# untitled.net
KiCad netlist of a schematic drawn in EAGLE
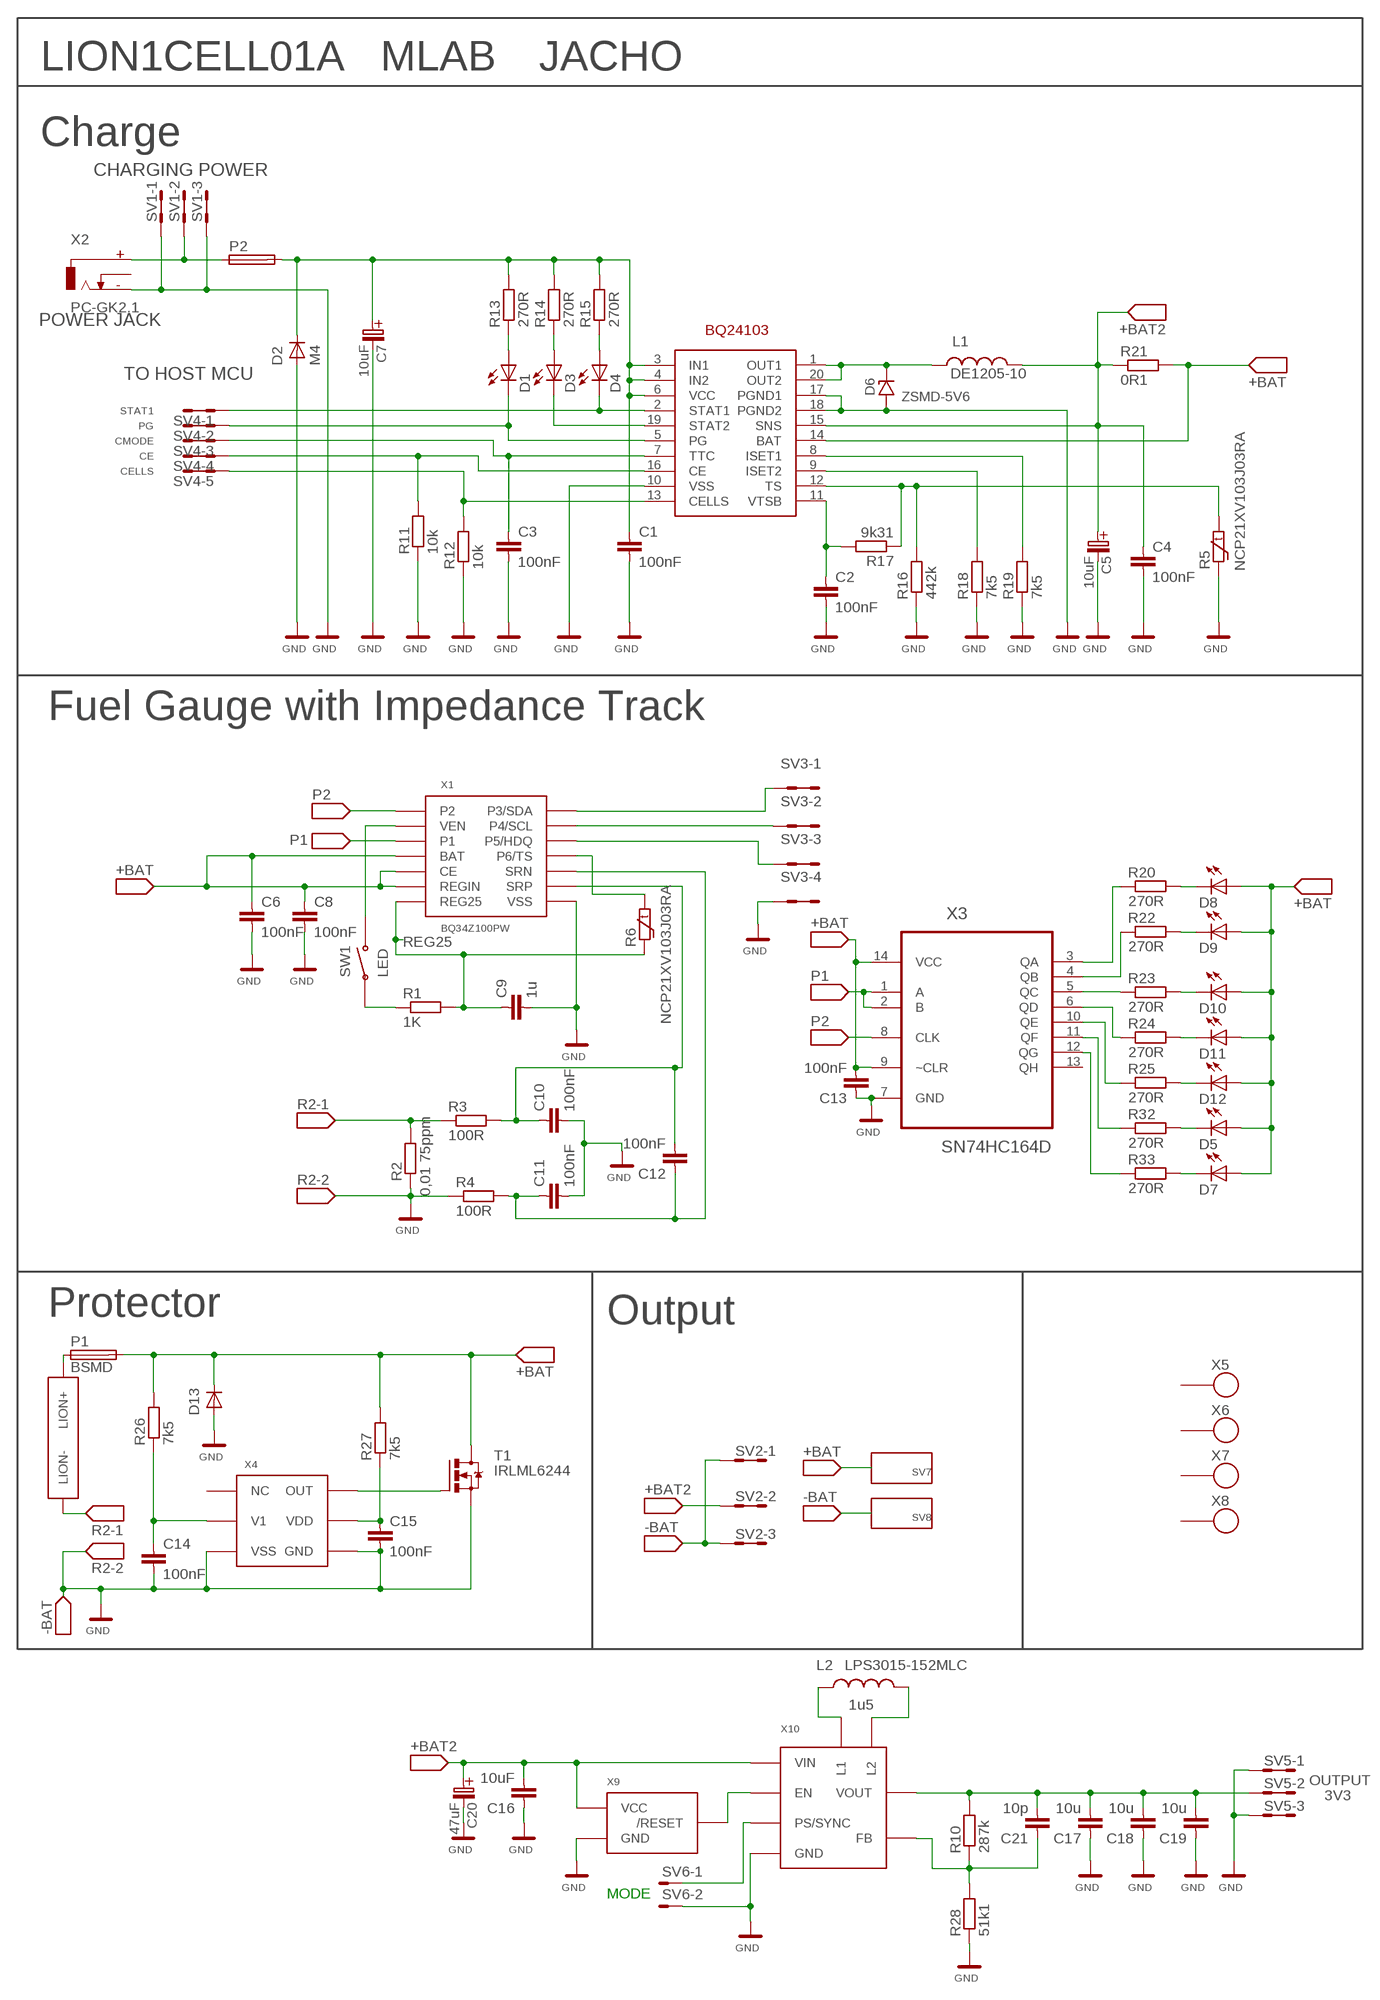
[diagram p0: schematic, sheet 1]

(export (version "E")
  (design (tool "Eeschema 10.0.6"))
  (components
    (comp (ref "C1")
      (value "100nF")
      (footprint "eagle-import:C0805")
      (libsource (lib "eagle-import") (part "C0805"))
    )
    (comp (ref "C2")
      (value "100nF")
      (footprint "eagle-import:C0805")
      (libsource (lib "eagle-import") (part "C0805"))
    )
    (comp (ref "C3")
      (value "100nF")
      (footprint "eagle-import:C0805")
      (libsource (lib "eagle-import") (part "C0805"))
    )
    (comp (ref "C4")
      (value "100nF")
      (footprint "eagle-import:C0805")
      (libsource (lib "eagle-import") (part "C0805"))
    )
    (comp (ref "C5") (value "10uF") (footprint "eagle-import:B") (libsource (lib "eagle-import") (part "B")))
    (comp (ref "C6")
      (value "100nF")
      (footprint "eagle-import:C0805")
      (libsource (lib "eagle-import") (part "C0805"))
    )
    (comp (ref "C7") (value "10uF") (footprint "eagle-import:B") (libsource (lib "eagle-import") (part "B")))
    (comp (ref "C8")
      (value "100nF")
      (footprint "eagle-import:C0805")
      (libsource (lib "eagle-import") (part "C0805"))
    )
    (comp (ref "C9")
      (value "1u")
      (footprint "eagle-import:C0805")
      (libsource (lib "eagle-import") (part "C0805"))
    )
    (comp (ref "C10")
      (value "100nF")
      (footprint "eagle-import:C0805")
      (libsource (lib "eagle-import") (part "C0805"))
    )
    (comp (ref "C11")
      (value "100nF")
      (footprint "eagle-import:C0805")
      (libsource (lib "eagle-import") (part "C0805"))
    )
    (comp (ref "C12")
      (value "100nF")
      (footprint "eagle-import:C0805")
      (libsource (lib "eagle-import") (part "C0805"))
    )
    (comp (ref "C13")
      (value "100nF")
      (footprint "eagle-import:C0805")
      (libsource (lib "eagle-import") (part "C0805"))
    )
    (comp (ref "C14")
      (value "100nF")
      (footprint "eagle-import:C0805")
      (libsource (lib "eagle-import") (part "C0805"))
    )
    (comp (ref "C15")
      (value "100nF")
      (footprint "eagle-import:C0805")
      (libsource (lib "eagle-import") (part "C0805"))
    )
    (comp (ref "C16")
      (value "10uF")
      (footprint "eagle-import:C0805")
      (libsource (lib "eagle-import") (part "C0805"))
    )
    (comp (ref "C17")
      (value "10u")
      (footprint "eagle-import:C0805")
      (libsource (lib "eagle-import") (part "C0805"))
    )
    (comp (ref "C18")
      (value "10u")
      (footprint "eagle-import:C0805")
      (libsource (lib "eagle-import") (part "C0805"))
    )
    (comp (ref "C19")
      (value "10u")
      (footprint "eagle-import:C0805")
      (libsource (lib "eagle-import") (part "C0805"))
    )
    (comp (ref "C20") (value "47uF") (footprint "eagle-import:B") (libsource (lib "eagle-import") (part "B")))
    (comp (ref "C21")
      (value "10p")
      (footprint "eagle-import:0603")
      (libsource (lib "eagle-import") (part "C0603"))
    )
    (comp (ref "D1")
      (value "LED1206_2")
      (footprint "eagle-import:1206_2")
      (libsource (lib "eagle-import") (part "LED1206_2"))
    )
    (comp (ref "D2")
      (value "M4")
      (footprint "eagle-import:SMB")
      (libsource (lib "eagle-import") (part "D-OB."))
    )
    (comp (ref "D3")
      (value "LED1206_2")
      (footprint "eagle-import:1206_2")
      (libsource (lib "eagle-import") (part "LED1206_2"))
    )
    (comp (ref "D4")
      (value "LED1206_2")
      (footprint "eagle-import:1206_2")
      (libsource (lib "eagle-import") (part "LED1206_2"))
    )
    (comp (ref "D5")
      (value "LED1206_2")
      (footprint "eagle-import:1206_2")
      (libsource (lib "eagle-import") (part "LED1206_2"))
    )
    (comp (ref "D6")
      (value "ZSMD-5V6")
      (footprint "eagle-import:MINIMELF")
      (libsource (lib "eagle-import") (part "D-ZENEROVA"))
    )
    (comp (ref "D7")
      (value "LED1206_2")
      (footprint "eagle-import:1206_2")
      (libsource (lib "eagle-import") (part "LED1206_2"))
    )
    (comp (ref "D8")
      (value "LED1206_2")
      (footprint "eagle-import:1206_2")
      (libsource (lib "eagle-import") (part "LED1206_2"))
    )
    (comp (ref "D9")
      (value "LED1206_2")
      (footprint "eagle-import:1206_2")
      (libsource (lib "eagle-import") (part "LED1206_2"))
    )
    (comp (ref "D10")
      (value "LED1206_2")
      (footprint "eagle-import:1206_2")
      (libsource (lib "eagle-import") (part "LED1206_2"))
    )
    (comp (ref "D11")
      (value "LED1206_2")
      (footprint "eagle-import:1206_2")
      (libsource (lib "eagle-import") (part "LED1206_2"))
    )
    (comp (ref "D12")
      (value "LED1206_2")
      (footprint "eagle-import:1206_2")
      (libsource (lib "eagle-import") (part "LED1206_2"))
    )
    (comp (ref "D13")
      (value "D-OB.SMA")
      (footprint "eagle-import:SMA")
      (libsource (lib "eagle-import") (part "D-OB.SMA"))
    )
    (comp (ref "L1")
      (value "DE1205-10")
      (footprint "eagle-import:DE1205-10")
      (libsource (lib "eagle-import") (part "DE1205-10"))
    )
    (comp (ref "L2")
      (value "LPS3015-152MLC")
      (footprint "eagle-import:LPS3015")
      (libsource (lib "eagle-import") (part "LPS3015"))
    )
    (comp (ref "P1")
      (value "BSMD")
      (footprint "eagle-import:2410")
      (libsource (lib "eagle-import") (part "POJISTKA2410"))
    )
    (comp (ref "P2")
      (value "POJISTKA_1812")
      (footprint "eagle-import:1812")
      (libsource (lib "eagle-import") (part "POJISTKA_1812"))
    )
    (comp (ref "R1")
      (value "1K")
      (footprint "eagle-import:0805")
      (libsource (lib "eagle-import") (part "R0805"))
    )
    (comp (ref "R2")
      (value "0,01 75ppm")
      (footprint "eagle-import:0805")
      (libsource (lib "eagle-import") (part "R0805"))
    )
    (comp (ref "R3")
      (value "100R")
      (footprint "eagle-import:0805")
      (libsource (lib "eagle-import") (part "R0805"))
    )
    (comp (ref "R4")
      (value "100R")
      (footprint "eagle-import:0805")
      (libsource (lib "eagle-import") (part "R0805"))
    )
    (comp (ref "R5")
      (value "NCP21XV103J03RA")
      (footprint "eagle-import:0805")
      (libsource (lib "eagle-import") (part "TERMISTOR0805"))
    )
    (comp (ref "R6")
      (value "NCP21XV103J03RA")
      (footprint "eagle-import:0805")
      (libsource (lib "eagle-import") (part "TERMISTOR0805"))
    )
    (comp (ref "R10")
      (value "287k")
      (footprint "eagle-import:0603")
      (libsource (lib "eagle-import") (part "R0603"))
    )
    (comp (ref "R11")
      (value "10k")
      (footprint "eagle-import:0805")
      (libsource (lib "eagle-import") (part "R0805"))
    )
    (comp (ref "R12")
      (value "10k")
      (footprint "eagle-import:0805")
      (libsource (lib "eagle-import") (part "R0805"))
    )
    (comp (ref "R13")
      (value "270R")
      (footprint "eagle-import:0805")
      (libsource (lib "eagle-import") (part "R0805"))
    )
    (comp (ref "R14")
      (value "270R")
      (footprint "eagle-import:0805")
      (libsource (lib "eagle-import") (part "R0805"))
    )
    (comp (ref "R15")
      (value "270R")
      (footprint "eagle-import:0805")
      (libsource (lib "eagle-import") (part "R0805"))
    )
    (comp (ref "R16")
      (value "442k")
      (footprint "eagle-import:0805")
      (libsource (lib "eagle-import") (part "R0805"))
    )
    (comp (ref "R17")
      (value "9k31")
      (footprint "eagle-import:0805")
      (libsource (lib "eagle-import") (part "R0805"))
    )
    (comp (ref "R18")
      (value "7k5")
      (footprint "eagle-import:0805")
      (libsource (lib "eagle-import") (part "R0805"))
    )
    (comp (ref "R19")
      (value "7k5")
      (footprint "eagle-import:0805")
      (libsource (lib "eagle-import") (part "R0805"))
    )
    (comp (ref "R20")
      (value "270R")
      (footprint "eagle-import:0805")
      (libsource (lib "eagle-import") (part "R0805"))
    )
    (comp (ref "R21")
      (value "0R1")
      (footprint "eagle-import:R2512")
      (libsource (lib "eagle-import") (part "R-EU_R2512"))
    )
    (comp (ref "R22")
      (value "270R")
      (footprint "eagle-import:0805")
      (libsource (lib "eagle-import") (part "R0805"))
    )
    (comp (ref "R23")
      (value "270R")
      (footprint "eagle-import:0805")
      (libsource (lib "eagle-import") (part "R0805"))
    )
    (comp (ref "R24")
      (value "270R")
      (footprint "eagle-import:0805")
      (libsource (lib "eagle-import") (part "R0805"))
    )
    (comp (ref "R25")
      (value "270R")
      (footprint "eagle-import:0805")
      (libsource (lib "eagle-import") (part "R0805"))
    )
    (comp (ref "R26")
      (value "7k5")
      (footprint "eagle-import:0805")
      (libsource (lib "eagle-import") (part "R0805"))
    )
    (comp (ref "R27")
      (value "7k5")
      (footprint "eagle-import:0805")
      (libsource (lib "eagle-import") (part "R0805"))
    )
    (comp (ref "R28")
      (value "51k1")
      (footprint "eagle-import:0603")
      (libsource (lib "eagle-import") (part "R0603"))
    )
    (comp (ref "R32")
      (value "270R")
      (footprint "eagle-import:0805")
      (libsource (lib "eagle-import") (part "R0805"))
    )
    (comp (ref "R33")
      (value "270R")
      (footprint "eagle-import:0805")
      (libsource (lib "eagle-import") (part "R0805"))
    )
    (comp (ref "SV1")
      (value "MA03-2")
      (footprint "eagle-import:MA03-2")
      (libsource (lib "eagle-import") (part "MA03-2"))
    )
    (comp (ref "SV2")
      (value "MA03-2")
      (footprint "eagle-import:MA03-2")
      (libsource (lib "eagle-import") (part "MA03-2"))
    )
    (comp (ref "SV3")
      (value "MA04-2")
      (footprint "eagle-import:MA04-2")
      (libsource (lib "eagle-import") (part "MA04-2"))
    )
    (comp (ref "SV4")
      (value "MA05-2")
      (footprint "eagle-import:MA05-2")
      (libsource (lib "eagle-import") (part "MA05-2"))
    )
    (comp (ref "SV5")
      (value "MA03-2")
      (footprint "eagle-import:MA03-2")
      (libsource (lib "eagle-import") (part "MA03-2"))
    )
    (comp (ref "SV6")
      (value "MA02-1")
      (footprint "eagle-import:MA02-1")
      (libsource (lib "eagle-import") (part "MA02-1"))
    )
    (comp (ref "SV7")
      (value "WAGO256")
      (footprint "eagle-import:WAGO256")
      (libsource (lib "eagle-import") (part "WAGO256"))
    )
    (comp (ref "SV8")
      (value "WAGO256")
      (footprint "eagle-import:WAGO256")
      (libsource (lib "eagle-import") (part "WAGO256"))
    )
    (comp (ref "SW1")
      (value "TACT-64K")
      (footprint "eagle-import:TACT-64K")
      (libsource (lib "eagle-import") (part "TACT-64K"))
    )
    (comp (ref "T1")
      (value "IRLML6244")
      (footprint "eagle-import:SOT23")
      (libsource (lib "eagle-import") (part "IRLML6244TRPBF"))
    )
    (comp (ref "U$2")
      (value "LION1")
      (footprint "eagle-import:LION1")
      (libsource (lib "eagle-import") (part "LION1"))
    )
    (comp (ref "U1")
      (value "BQ24103")
      (footprint "eagle-import:RHL_R-VQFN-N20")
      (libsource (lib "eagle-import") (part "BQ24103"))
    )
    (comp (ref "X1")
      (value "BQ34Z100PW")
      (footprint "eagle-import:TSSOP14")
      (libsource (lib "eagle-import") (part "BQ34Z100PW"))
    )
    (comp (ref "X2")
      (value "DC2.1MM")
      (footprint "eagle-import:DC2.1MM")
      (libsource (lib "eagle-import") (part "DC2.1MM"))
    )
    (comp (ref "X3")
      (value "SN74HC164D")
      (footprint "eagle-import:SOIC127P600X175-14N")
      (libsource (lib "eagle-import") (part "SN74HC164D"))
    )
    (comp (ref "X4")
      (value "BQ294602")
      (footprint "eagle-import:SON_N6")
      (libsource (lib "eagle-import") (part "BQ294602"))
    )
    (comp (ref "X5")
      (value "SROUB3M")
      (footprint "eagle-import:SROUB3M")
      (libsource (lib "eagle-import") (part "SROUB3M"))
    )
    (comp (ref "X6")
      (value "SROUB3M")
      (footprint "eagle-import:SROUB3M")
      (libsource (lib "eagle-import") (part "SROUB3M"))
    )
    (comp (ref "X7")
      (value "SROUB3M")
      (footprint "eagle-import:SROUB3M")
      (libsource (lib "eagle-import") (part "SROUB3M"))
    )
    (comp (ref "X8")
      (value "SROUB3M")
      (footprint "eagle-import:SROUB3M")
      (libsource (lib "eagle-import") (part "SROUB3M"))
    )
    (comp (ref "X9")
      (value "APX809-26SA")
      (footprint "eagle-import:SOT23")
      (libsource (lib "eagle-import") (part "APX809-26SA"))
    )
    (comp (ref "X10")
      (value "TPS63036")
      (footprint "eagle-import:DSBGA8")
      (libsource (lib "eagle-import") (part "TPS63036"))
    )
  )
  (nets
    (net (code "1") (name "/+BAT") (class "Default")
      (node (ref "C13") (pin "2") (pinfunction "2_2") (pintype "passive"))
      (node (ref "C6") (pin "1") (pinfunction "1_1") (pintype "passive"))
      (node (ref "C8") (pin "1") (pinfunction "1_1") (pintype "passive"))
      (node (ref "D10") (pin "A") (pinfunction "A_A") (pintype "passive"))
      (node (ref "D11") (pin "A") (pinfunction "A_A") (pintype "passive"))
      (node (ref "D12") (pin "A") (pinfunction "A_A") (pintype "passive"))
      (node (ref "D13") (pin "K") (pinfunction "C_K") (pintype "passive"))
      (node (ref "D5") (pin "A") (pinfunction "A_A") (pintype "passive"))
      (node (ref "D7") (pin "A") (pinfunction "A_A") (pintype "passive"))
      (node (ref "D8") (pin "A") (pinfunction "A_A") (pintype "passive"))
      (node (ref "D9") (pin "A") (pinfunction "A_A") (pintype "passive"))
      (node (ref "P1") (pin "2") (pinfunction "2_2") (pintype "passive"))
      (node (ref "R21") (pin "2") (pinfunction "2_2") (pintype "passive"))
      (node (ref "R26") (pin "2") (pinfunction "2_2") (pintype "passive"))
      (node (ref "R27") (pin "2") (pinfunction "2_2") (pintype "passive"))
      (node (ref "SV7") (pin "1") (pinfunction "P$1_1") (pintype "passive"))
      (node (ref "SV7") (pin "A1") (pinfunction "P$1_A1") (pintype "passive"))
      (node (ref "T1") (pin "3") (pinfunction "D_3") (pintype "passive"))
      (node (ref "U1") (pin "14") (pinfunction "BAT_14") (pintype "bidirectional"))
      (node (ref "X1") (pin "4") (pinfunction "BAT_4") (pintype "bidirectional"))
      (node (ref "X1") (pin "5") (pinfunction "CE_5") (pintype "bidirectional"))
      (node (ref "X1") (pin "6") (pinfunction "REGIN_6") (pintype "bidirectional"))
      (node (ref "X3") (pin "14") (pinfunction "VCC_14") (pintype "power_in"))
      (node (ref "X3") (pin "9") (pinfunction "~{CLR}_9") (pintype "input"))
    )
    (net (code "2") (name "/+BAT2") (class "Default")
      (node (ref "C16") (pin "2") (pinfunction "2_2") (pintype "passive"))
      (node (ref "C20") (pin "+") (pinfunction "C_EL+_+") (pintype "passive"))
      (node (ref "C4") (pin "1") (pinfunction "1_1") (pintype "passive"))
      (node (ref "C5") (pin "+") (pinfunction "C_EL+_+") (pintype "passive"))
      (node (ref "L1") (pin "P$2") (pinfunction "2_P$2") (pintype "passive"))
      (node (ref "R21") (pin "1") (pinfunction "1_1") (pintype "passive"))
      (node (ref "SV2") (pin "3") (pinfunction "K_3") (pintype "passive"))
      (node (ref "SV2") (pin "4") (pinfunction "K_4") (pintype "passive"))
      (node (ref "U1") (pin "15") (pinfunction "SNS_15") (pintype "bidirectional"))
      (node (ref "X10") (pin "A1") (pinfunction "VIN_A1") (pintype "input"))
      (node (ref "X9") (pin "3") (pinfunction "VCC_3") (pintype "input"))
    )
    (net (code "3") (name "/P1") (class "Default")
      (node (ref "X1") (pin "3") (pinfunction "P1_3") (pintype "bidirectional"))
      (node (ref "X3") (pin "1") (pinfunction "A_1") (pintype "input"))
      (node (ref "X3") (pin "2") (pinfunction "B_2") (pintype "input"))
    )
    (net (code "4") (name "/P2") (class "Default")
      (node (ref "X1") (pin "1") (pinfunction "P2_1") (pintype "bidirectional"))
      (node (ref "X3") (pin "8") (pinfunction "CLK_8") (pintype "input"))
    )
    (net (code "5") (name "/R2") (class "Default")
      (node (ref "R2") (pin "2") (pinfunction "2_2") (pintype "passive"))
      (node (ref "R3") (pin "1") (pinfunction "1_1") (pintype "passive"))
      (node (ref "U$2") (pin "-") (pinfunction "LION-_-") (pintype "bidirectional"))
      (node (ref "U$2") (pin "-1") (pinfunction "LION-_-1") (pintype "bidirectional"))
    )
    (net (code "6") (name "GND") (class "Default")
      (node (ref "C1") (pin "2") (pinfunction "2_2") (pintype "passive"))
      (node (ref "C10") (pin "2") (pinfunction "2_2") (pintype "passive"))
      (node (ref "C11") (pin "2") (pinfunction "2_2") (pintype "passive"))
      (node (ref "C13") (pin "1") (pinfunction "1_1") (pintype "passive"))
      (node (ref "C14") (pin "2") (pinfunction "2_2") (pintype "passive"))
      (node (ref "C15") (pin "2") (pinfunction "2_2") (pintype "passive"))
      (node (ref "C16") (pin "1") (pinfunction "1_1") (pintype "passive"))
      (node (ref "C17") (pin "1") (pinfunction "1_1") (pintype "passive"))
      (node (ref "C18") (pin "1") (pinfunction "1_1") (pintype "passive"))
      (node (ref "C19") (pin "1") (pinfunction "1_1") (pintype "passive"))
      (node (ref "C2") (pin "2") (pinfunction "2_2") (pintype "passive"))
      (node (ref "C20") (pin "-") (pinfunction "C_EL-_-") (pintype "passive"))
      (node (ref "C3") (pin "2") (pinfunction "2_2") (pintype "passive"))
      (node (ref "C4") (pin "2") (pinfunction "2_2") (pintype "passive"))
      (node (ref "C5") (pin "-") (pinfunction "C_EL-_-") (pintype "passive"))
      (node (ref "C6") (pin "2") (pinfunction "2_2") (pintype "passive"))
      (node (ref "C7") (pin "-") (pinfunction "C_EL-_-") (pintype "passive"))
      (node (ref "C8") (pin "2") (pinfunction "2_2") (pintype "passive"))
      (node (ref "C9") (pin "2") (pinfunction "2_2") (pintype "passive"))
      (node (ref "D13") (pin "A") (pinfunction "A_A") (pintype "passive"))
      (node (ref "D2") (pin "A") (pinfunction "A_A") (pintype "passive"))
      (node (ref "D6") (pin "A") (pinfunction "A_A") (pintype "passive"))
      (node (ref "R11") (pin "1") (pinfunction "1_1") (pintype "passive"))
      (node (ref "R12") (pin "1") (pinfunction "1_1") (pintype "passive"))
      (node (ref "R16") (pin "1") (pinfunction "1_1") (pintype "passive"))
      (node (ref "R18") (pin "1") (pinfunction "1_1") (pintype "passive"))
      (node (ref "R19") (pin "1") (pinfunction "1_1") (pintype "passive"))
      (node (ref "R2") (pin "1") (pinfunction "1_1") (pintype "passive"))
      (node (ref "R28") (pin "1") (pinfunction "1_1") (pintype "passive"))
      (node (ref "R4") (pin "1") (pinfunction "1_1") (pintype "passive"))
      (node (ref "R5") (pin "1") (pinfunction "1_1") (pintype "passive"))
      (node (ref "SV1") (pin "1") (pinfunction "K_1") (pintype "passive"))
      (node (ref "SV1") (pin "2") (pinfunction "K_2") (pintype "passive"))
      (node (ref "SV1") (pin "5") (pinfunction "K_5") (pintype "passive"))
      (node (ref "SV1") (pin "6") (pinfunction "K_6") (pintype "passive"))
      (node (ref "SV2") (pin "1") (pinfunction "K_1") (pintype "passive"))
      (node (ref "SV2") (pin "2") (pinfunction "K_2") (pintype "passive"))
      (node (ref "SV2") (pin "5") (pinfunction "K_5") (pintype "passive"))
      (node (ref "SV2") (pin "6") (pinfunction "K_6") (pintype "passive"))
      (node (ref "SV3") (pin "7") (pinfunction "K_7") (pintype "passive"))
      (node (ref "SV3") (pin "8") (pinfunction "K_8") (pintype "passive"))
      (node (ref "SV5") (pin "1") (pinfunction "K_1") (pintype "passive"))
      (node (ref "SV5") (pin "2") (pinfunction "K_2") (pintype "passive"))
      (node (ref "SV5") (pin "5") (pinfunction "K_5") (pintype "passive"))
      (node (ref "SV5") (pin "6") (pinfunction "K_6") (pintype "passive"))
      (node (ref "SV6") (pin "2") (pinfunction "P$1_2") (pintype "passive"))
      (node (ref "SV8") (pin "1") (pinfunction "P$1_1") (pintype "passive"))
      (node (ref "SV8") (pin "A1") (pinfunction "P$1_A1") (pintype "passive"))
      (node (ref "T1") (pin "2") (pinfunction "S_2") (pintype "passive"))
      (node (ref "U1") (pin "10") (pinfunction "VSS_10") (pintype "bidirectional"))
      (node (ref "U1") (pin "17") (pinfunction "PGND1_17") (pintype "bidirectional"))
      (node (ref "U1") (pin "18") (pinfunction "PGND2_18") (pintype "bidirectional"))
      (node (ref "X1") (pin "8") (pinfunction "VSS_8") (pintype "bidirectional"))
      (node (ref "X10") (pin "C2") (pinfunction "GND_C2") (pintype "passive"))
      (node (ref "X2") (pin "GND") (pinfunction "-_GND") (pintype "passive"))
      (node (ref "X3") (pin "7") (pinfunction "GND_7") (pintype "passive"))
      (node (ref "X4") (pin "3") (pinfunction "VSS_3") (pintype "bidirectional"))
      (node (ref "X4") (pin "4") (pinfunction "VSS_4") (pintype "bidirectional"))
      (node (ref "X4") (pin "7") (pinfunction "GND_7") (pintype "bidirectional"))
      (node (ref "X9") (pin "1") (pinfunction "GND_1") (pintype "passive"))
    )
    (net (code "7") (name "Net-(C7-C_EL+)") (class "Default")
      (node (ref "C1") (pin "1") (pinfunction "1_1") (pintype "passive"))
      (node (ref "C7") (pin "+") (pinfunction "C_EL+_+") (pintype "passive"))
      (node (ref "D2") (pin "K") (pinfunction "C_K") (pintype "passive"))
      (node (ref "P2") (pin "2") (pinfunction "2_2") (pintype "passive"))
      (node (ref "R13") (pin "2") (pinfunction "2_2") (pintype "passive"))
      (node (ref "R14") (pin "2") (pinfunction "2_2") (pintype "passive"))
      (node (ref "R15") (pin "2") (pinfunction "2_2") (pintype "passive"))
      (node (ref "U1") (pin "3") (pinfunction "IN1_3") (pintype "bidirectional"))
      (node (ref "U1") (pin "4") (pinfunction "IN2_4") (pintype "bidirectional"))
      (node (ref "U1") (pin "6") (pinfunction "VCC_6") (pintype "bidirectional"))
    )
    (net (code "8") (name "Net-(D1-C)") (class "Default")
      (node (ref "D1") (pin "K") (pinfunction "C_K") (pintype "passive"))
      (node (ref "SV4") (pin "3") (pinfunction "K_3") (pintype "passive"))
      (node (ref "SV4") (pin "4") (pinfunction "K_4") (pintype "passive"))
      (node (ref "U1") (pin "5") (pinfunction "PG_5") (pintype "bidirectional"))
    )
    (net (code "9") (name "Net-(D1-PadA)") (class "Default")
      (node (ref "D1") (pin "A") (pinfunction "A_A") (pintype "passive"))
      (node (ref "R13") (pin "1") (pinfunction "1_1") (pintype "passive"))
    )
    (net (code "10") (name "Net-(D3-C)") (class "Default")
      (node (ref "D3") (pin "K") (pinfunction "C_K") (pintype "passive"))
      (node (ref "U1") (pin "19") (pinfunction "STAT2_19") (pintype "bidirectional"))
    )
    (net (code "11") (name "Net-(D3-PadA)") (class "Default")
      (node (ref "D3") (pin "A") (pinfunction "A_A") (pintype "passive"))
      (node (ref "R14") (pin "1") (pinfunction "1_1") (pintype "passive"))
    )
    (net (code "12") (name "Net-(D4-C)") (class "Default")
      (node (ref "D4") (pin "K") (pinfunction "C_K") (pintype "passive"))
      (node (ref "SV4") (pin "1") (pinfunction "K_1") (pintype "passive"))
      (node (ref "SV4") (pin "2") (pinfunction "K_2") (pintype "passive"))
      (node (ref "U1") (pin "2") (pinfunction "STAT1_2") (pintype "bidirectional"))
    )
    (net (code "13") (name "Net-(D4-PadA)") (class "Default")
      (node (ref "D4") (pin "A") (pinfunction "A_A") (pintype "passive"))
      (node (ref "R15") (pin "1") (pinfunction "1_1") (pintype "passive"))
    )
    (net (code "14") (name "Net-(D5-C)") (class "Default")
      (node (ref "D5") (pin "K") (pinfunction "C_K") (pintype "passive"))
      (node (ref "R32") (pin "2") (pinfunction "2_2") (pintype "passive"))
    )
    (net (code "15") (name "Net-(D6-K)") (class "Default")
      (node (ref "D6") (pin "C") (pinfunction "K_C") (pintype "passive"))
      (node (ref "L1") (pin "P$1") (pinfunction "1_P$1") (pintype "passive"))
      (node (ref "U1") (pin "1") (pinfunction "OUT1_1") (pintype "bidirectional"))
      (node (ref "U1") (pin "20") (pinfunction "OUT2_20") (pintype "bidirectional"))
    )
    (net (code "16") (name "Net-(D7-C)") (class "Default")
      (node (ref "D7") (pin "K") (pinfunction "C_K") (pintype "passive"))
      (node (ref "R33") (pin "2") (pinfunction "2_2") (pintype "passive"))
    )
    (net (code "17") (name "Net-(D8-C)") (class "Default")
      (node (ref "D8") (pin "K") (pinfunction "C_K") (pintype "passive"))
      (node (ref "R20") (pin "2") (pinfunction "2_2") (pintype "passive"))
    )
    (net (code "18") (name "Net-(D9-C)") (class "Default")
      (node (ref "D9") (pin "K") (pinfunction "C_K") (pintype "passive"))
      (node (ref "R22") (pin "2") (pinfunction "2_2") (pintype "passive"))
    )
    (net (code "19") (name "Net-(D10-C)") (class "Default")
      (node (ref "D10") (pin "K") (pinfunction "C_K") (pintype "passive"))
      (node (ref "R23") (pin "2") (pinfunction "2_2") (pintype "passive"))
    )
    (net (code "20") (name "Net-(D11-C)") (class "Default")
      (node (ref "D11") (pin "K") (pinfunction "C_K") (pintype "passive"))
      (node (ref "R24") (pin "2") (pinfunction "2_2") (pintype "passive"))
    )
    (net (code "21") (name "Net-(D12-C)") (class "Default")
      (node (ref "D12") (pin "K") (pinfunction "C_K") (pintype "passive"))
      (node (ref "R25") (pin "2") (pinfunction "2_2") (pintype "passive"))
    )
    (net (code "22") (name "Net-(P1-Pad1)") (class "Default")
      (node (ref "P1") (pin "1") (pinfunction "1_1") (pintype "passive"))
      (node (ref "U$2") (pin "+") (pinfunction "LION+_+") (pintype "bidirectional"))
      (node (ref "U$2") (pin "+1") (pinfunction "LION+_+1") (pintype "bidirectional"))
    )
    (net (code "23") (name "Net-(P2-Pad1)") (class "Default")
      (node (ref "P2") (pin "1") (pinfunction "1_1") (pintype "passive"))
      (node (ref "SV1") (pin "3") (pinfunction "K_3") (pintype "passive"))
      (node (ref "SV1") (pin "4") (pinfunction "K_4") (pintype "passive"))
      (node (ref "X2") (pin "+") (pinfunction "+_+") (pintype "passive"))
    )
    (net (code "24") (name "Net-(R1-Pad1)") (class "Default")
      (node (ref "R1") (pin "1") (pinfunction "1_1") (pintype "passive"))
      (node (ref "SW1") (pin "P$1") (pinfunction "P$1_P$1") (pintype "passive"))
      (node (ref "SW1") (pin "P$2") (pinfunction "P$1_P$2") (pintype "passive"))
    )
    (net (code "25") (name "Net-(SV6A-P$1)") (class "Default")
      (node (ref "SV6") (pin "1") (pinfunction "P$1_1") (pintype "passive"))
      (node (ref "X10") (pin "B2") (pinfunction "PS/SYNC_B2") (pintype "input"))
    )
    (net (code "26") (name "Net-(T1-G)") (class "Default")
      (node (ref "T1") (pin "1") (pinfunction "G_1") (pintype "passive"))
      (node (ref "X4") (pin "6") (pinfunction "OUT_6") (pintype "bidirectional"))
    )
    (net (code "27") (name "Net-(U1-CE)") (class "Default")
      (node (ref "R11") (pin "2") (pinfunction "2_2") (pintype "passive"))
      (node (ref "SV4") (pin "7") (pinfunction "K_7") (pintype "passive"))
      (node (ref "SV4") (pin "8") (pinfunction "K_8") (pintype "passive"))
      (node (ref "U1") (pin "16") (pinfunction "CE_16") (pintype "bidirectional"))
    )
    (net (code "28") (name "Net-(U1-CELLS)") (class "Default")
      (node (ref "R12") (pin "2") (pinfunction "2_2") (pintype "passive"))
      (node (ref "SV4") (pin "10") (pinfunction "K_10") (pintype "passive"))
      (node (ref "SV4") (pin "9") (pinfunction "K_9") (pintype "passive"))
      (node (ref "U1") (pin "13") (pinfunction "CELLS_13") (pintype "bidirectional"))
    )
    (net (code "29") (name "Net-(U1-ISET1)") (class "Default")
      (node (ref "R19") (pin "2") (pinfunction "2_2") (pintype "passive"))
      (node (ref "U1") (pin "8") (pinfunction "ISET1_8") (pintype "bidirectional"))
    )
    (net (code "30") (name "Net-(U1-ISET2)") (class "Default")
      (node (ref "R18") (pin "2") (pinfunction "2_2") (pintype "passive"))
      (node (ref "U1") (pin "9") (pinfunction "ISET2_9") (pintype "bidirectional"))
    )
    (net (code "31") (name "Net-(U1-TS)") (class "Default")
      (node (ref "R16") (pin "2") (pinfunction "2_2") (pintype "passive"))
      (node (ref "R17") (pin "1") (pinfunction "1_1") (pintype "passive"))
      (node (ref "R5") (pin "2") (pinfunction "2_2") (pintype "passive"))
      (node (ref "U1") (pin "12") (pinfunction "TS_12") (pintype "bidirectional"))
    )
    (net (code "32") (name "Net-(U1-TTC)") (class "Default")
      (node (ref "C3") (pin "1") (pinfunction "1_1") (pintype "passive"))
      (node (ref "SV4") (pin "5") (pinfunction "K_5") (pintype "passive"))
      (node (ref "SV4") (pin "6") (pinfunction "K_6") (pintype "passive"))
      (node (ref "U1") (pin "7") (pinfunction "TTC_7") (pintype "bidirectional"))
    )
    (net (code "33") (name "Net-(U1-VTSB)") (class "Default")
      (node (ref "C2") (pin "1") (pinfunction "1_1") (pintype "passive"))
      (node (ref "R17") (pin "2") (pinfunction "2_2") (pintype "passive"))
      (node (ref "U1") (pin "11") (pinfunction "VTSB_11") (pintype "bidirectional"))
    )
    (net (code "34") (name "Net-(X1-P3{slash}SDA)") (class "Default")
      (node (ref "SV3") (pin "1") (pinfunction "K_1") (pintype "passive"))
      (node (ref "SV3") (pin "2") (pinfunction "K_2") (pintype "passive"))
      (node (ref "X1") (pin "14") (pinfunction "P3/SDA_14") (pintype "bidirectional"))
    )
    (net (code "35") (name "Net-(X1-P4{slash}SCL)") (class "Default")
      (node (ref "SV3") (pin "3") (pinfunction "K_3") (pintype "passive"))
      (node (ref "SV3") (pin "4") (pinfunction "K_4") (pintype "passive"))
      (node (ref "X1") (pin "13") (pinfunction "P4/SCL_13") (pintype "bidirectional"))
    )
    (net (code "36") (name "Net-(X1-P5{slash}HDQ)") (class "Default")
      (node (ref "SV3") (pin "5") (pinfunction "K_5") (pintype "passive"))
      (node (ref "SV3") (pin "6") (pinfunction "K_6") (pintype "passive"))
      (node (ref "X1") (pin "12") (pinfunction "P5/HDQ_12") (pintype "bidirectional"))
    )
    (net (code "37") (name "Net-(X1-P6{slash}TS)") (class "Default")
      (node (ref "R6") (pin "2") (pinfunction "2_2") (pintype "passive"))
      (node (ref "X1") (pin "11") (pinfunction "P6/TS_11") (pintype "bidirectional"))
    )
    (net (code "38") (name "Net-(X1-REG25)") (class "Default")
      (node (ref "C9") (pin "1") (pinfunction "1_1") (pintype "passive"))
      (node (ref "R1") (pin "2") (pinfunction "2_2") (pintype "passive"))
      (node (ref "R6") (pin "1") (pinfunction "1_1") (pintype "passive"))
      (node (ref "X1") (pin "7") (pinfunction "REG25_7") (pintype "bidirectional"))
    )
    (net (code "39") (name "Net-(X1-SRN)") (class "Default")
      (node (ref "C11") (pin "1") (pinfunction "1_1") (pintype "passive"))
      (node (ref "C12") (pin "1") (pinfunction "1_1") (pintype "passive"))
      (node (ref "R4") (pin "2") (pinfunction "2_2") (pintype "passive"))
      (node (ref "X1") (pin "10") (pinfunction "SRN_10") (pintype "bidirectional"))
    )
    (net (code "40") (name "Net-(X1-SRP)") (class "Default")
      (node (ref "C10") (pin "1") (pinfunction "1_1") (pintype "passive"))
      (node (ref "C12") (pin "2") (pinfunction "2_2") (pintype "passive"))
      (node (ref "R3") (pin "2") (pinfunction "2_2") (pintype "passive"))
      (node (ref "X1") (pin "9") (pinfunction "SRP_9") (pintype "bidirectional"))
    )
    (net (code "41") (name "Net-(X1-VEN)") (class "Default")
      (node (ref "SW1") (pin "P$3") (pinfunction "P$2_P$3") (pintype "passive"))
      (node (ref "SW1") (pin "P$4") (pinfunction "P$2_P$4") (pintype "passive"))
      (node (ref "X1") (pin "2") (pinfunction "VEN_2") (pintype "bidirectional"))
    )
    (net (code "42") (name "Net-(X3-QA)") (class "Default")
      (node (ref "R20") (pin "1") (pinfunction "1_1") (pintype "passive"))
      (node (ref "X3") (pin "3") (pinfunction "QA_3") (pintype "output"))
    )
    (net (code "43") (name "Net-(X3-QB)") (class "Default")
      (node (ref "R22") (pin "1") (pinfunction "1_1") (pintype "passive"))
      (node (ref "X3") (pin "4") (pinfunction "QB_4") (pintype "output"))
    )
    (net (code "44") (name "Net-(X3-QC)") (class "Default")
      (node (ref "R23") (pin "1") (pinfunction "1_1") (pintype "passive"))
      (node (ref "X3") (pin "5") (pinfunction "QC_5") (pintype "output"))
    )
    (net (code "45") (name "Net-(X3-QD)") (class "Default")
      (node (ref "R24") (pin "1") (pinfunction "1_1") (pintype "passive"))
      (node (ref "X3") (pin "6") (pinfunction "QD_6") (pintype "output"))
    )
    (net (code "46") (name "Net-(X3-QE)") (class "Default")
      (node (ref "R25") (pin "1") (pinfunction "1_1") (pintype "passive"))
      (node (ref "X3") (pin "10") (pinfunction "QE_10") (pintype "output"))
    )
    (net (code "47") (name "Net-(X3-QF)") (class "Default")
      (node (ref "R32") (pin "1") (pinfunction "1_1") (pintype "passive"))
      (node (ref "X3") (pin "11") (pinfunction "QF_11") (pintype "output"))
    )
    (net (code "48") (name "Net-(X3-QG)") (class "Default")
      (node (ref "R33") (pin "1") (pinfunction "1_1") (pintype "passive"))
      (node (ref "X3") (pin "12") (pinfunction "QG_12") (pintype "output"))
    )
    (net (code "49") (name "Net-(X4-V1)") (class "Default")
      (node (ref "C14") (pin "1") (pinfunction "1_1") (pintype "passive"))
      (node (ref "R26") (pin "1") (pinfunction "1_1") (pintype "passive"))
      (node (ref "X4") (pin "2") (pinfunction "V1_2") (pintype "bidirectional"))
    )
    (net (code "50") (name "Net-(X4-VDD)") (class "Default")
      (node (ref "C15") (pin "1") (pinfunction "1_1") (pintype "passive"))
      (node (ref "R27") (pin "1") (pinfunction "1_1") (pintype "passive"))
      (node (ref "X4") (pin "5") (pinfunction "VDD_5") (pintype "bidirectional"))
    )
    (net (code "51") (name "Net-(X10-EN)") (class "Default")
      (node (ref "X10") (pin "A2") (pinfunction "EN_A2") (pintype "input"))
      (node (ref "X9") (pin "2") (pinfunction "/RESET_2") (pintype "passive"))
    )
    (net (code "52") (name "Net-(X10-FB)") (class "Default")
      (node (ref "C21") (pin "1") (pinfunction "1_1") (pintype "passive"))
      (node (ref "R10") (pin "1") (pinfunction "1_1") (pintype "passive"))
      (node (ref "R28") (pin "2") (pinfunction "2_2") (pintype "passive"))
      (node (ref "X10") (pin "D2") (pinfunction "FB_D2") (pintype "input"))
    )
    (net (code "53") (name "Net-(X10-L1)") (class "Default")
      (node (ref "L2") (pin "1-1") (pinfunction "1_1-1") (pintype "passive"))
      (node (ref "L2") (pin "1-2") (pinfunction "1_1-2") (pintype "passive"))
      (node (ref "L2") (pin "1-3") (pinfunction "1_1-3") (pintype "passive"))
      (node (ref "X10") (pin "B1") (pinfunction "L1_B1") (pintype "passive"))
    )
    (net (code "54") (name "Net-(X10-L2)") (class "Default")
      (node (ref "L2") (pin "2-1") (pinfunction "2_2-1") (pintype "passive"))
      (node (ref "L2") (pin "2-2") (pinfunction "2_2-2") (pintype "passive"))
      (node (ref "L2") (pin "2-3") (pinfunction "2_2-3") (pintype "passive"))
      (node (ref "X10") (pin "C1") (pinfunction "L2_C1") (pintype "passive"))
    )
    (net (code "55") (name "Net-(X10-VOUT)") (class "Default")
      (node (ref "C17") (pin "2") (pinfunction "2_2") (pintype "passive"))
      (node (ref "C18") (pin "2") (pinfunction "2_2") (pintype "passive"))
      (node (ref "C19") (pin "2") (pinfunction "2_2") (pintype "passive"))
      (node (ref "C21") (pin "2") (pinfunction "2_2") (pintype "passive"))
      (node (ref "R10") (pin "2") (pinfunction "2_2") (pintype "passive"))
      (node (ref "SV5") (pin "3") (pinfunction "K_3") (pintype "passive"))
      (node (ref "SV5") (pin "4") (pinfunction "K_4") (pintype "passive"))
      (node (ref "X10") (pin "D1") (pinfunction "VOUT_D1") (pintype "output"))
    )
    (net (code "56") (name "unconnected-(X2-PadSW)") (class "Default")
      (node (ref "X2") (pin "SW") (pinfunction "SW_SW") (pintype "passive"))
    )
    (net (code "57") (name "unconnected-(X3-QH-Pad13)") (class "Default")
      (node (ref "X3") (pin "13") (pinfunction "QH_13") (pintype "output"))
    )
    (net (code "58") (name "unconnected-(X4-NC-Pad1)") (class "Default")
      (node (ref "X4") (pin "1") (pinfunction "NC_1") (pintype "bidirectional"))
    )
    (net (code "59") (name "unconnected-(X5-PadP$1)") (class "Default")
      (node (ref "X5") (pin "P$1") (pinfunction "P$1_P$1") (pintype "bidirectional"))
    )
    (net (code "60") (name "unconnected-(X6-PadP$1)") (class "Default")
      (node (ref "X6") (pin "P$1") (pinfunction "P$1_P$1") (pintype "bidirectional"))
    )
    (net (code "61") (name "unconnected-(X7-PadP$1)") (class "Default")
      (node (ref "X7") (pin "P$1") (pinfunction "P$1_P$1") (pintype "bidirectional"))
    )
    (net (code "62") (name "unconnected-(X8-PadP$1)") (class "Default")
      (node (ref "X8") (pin "P$1") (pinfunction "P$1_P$1") (pintype "bidirectional"))
    )
  )
)
